# 03_-_OUT__5V7_OCXO_PROTECTION.net
KiCad netlist of a schematic drawn in Altium Designer
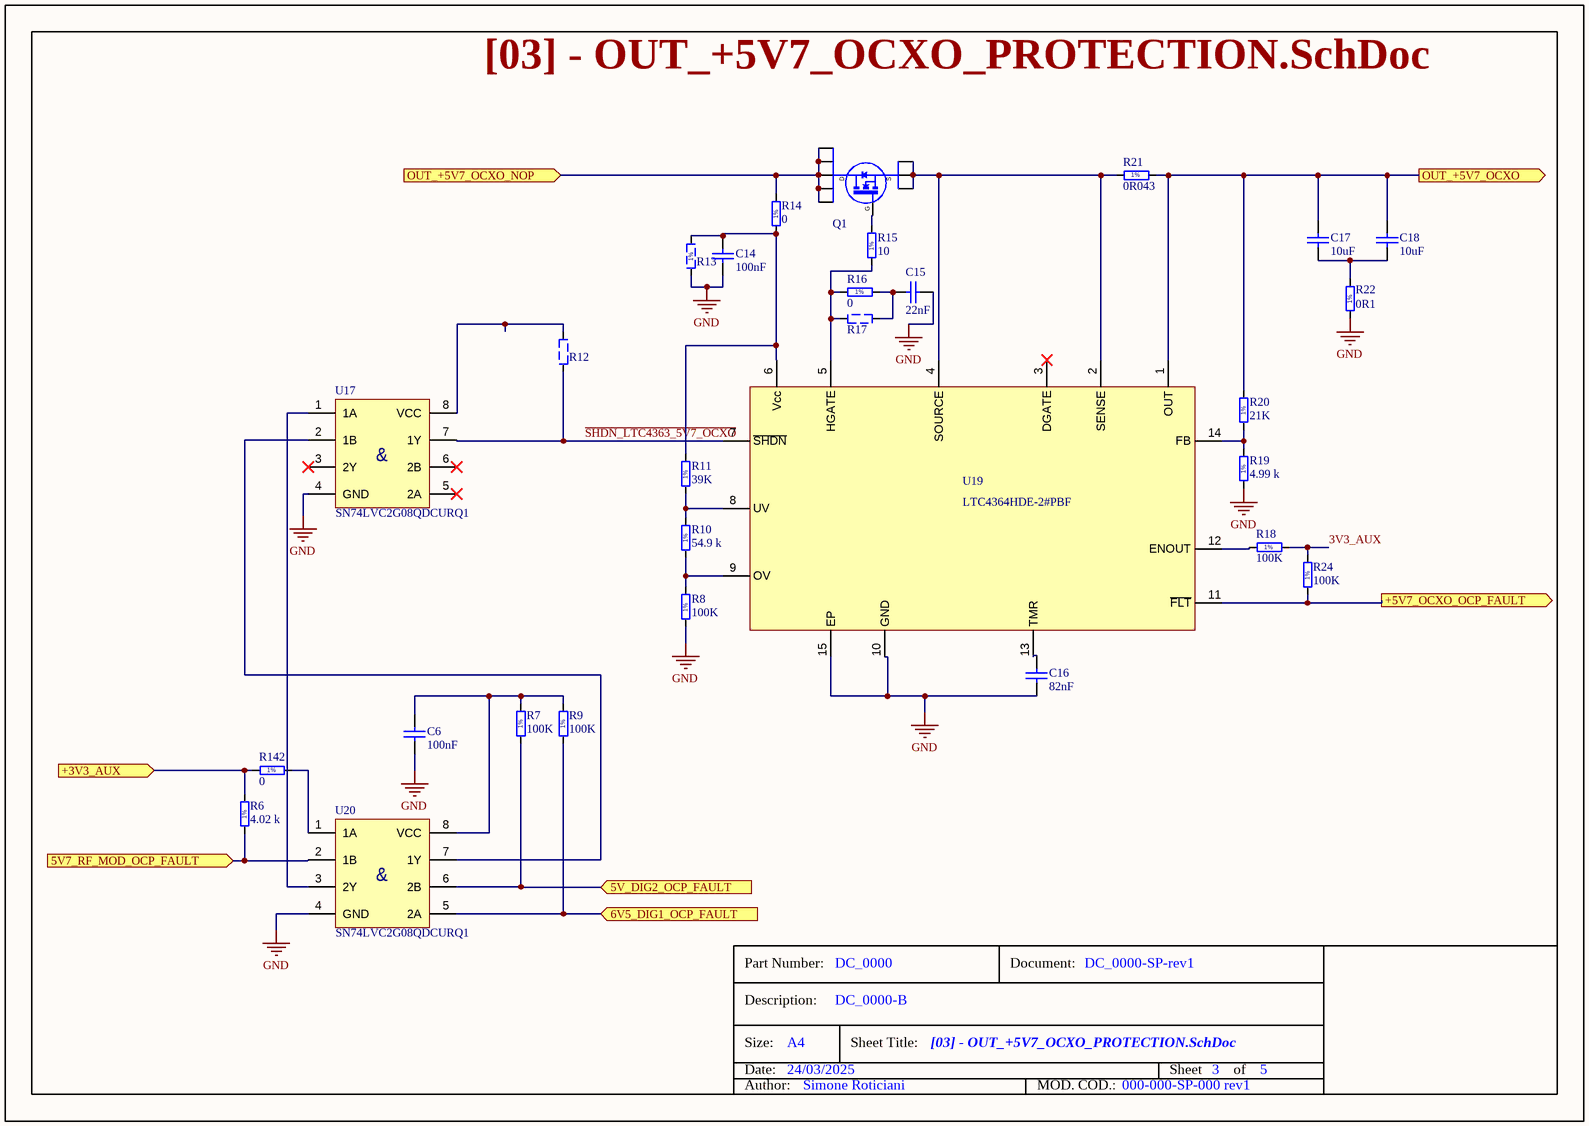
[diagram p0: [03] - OUT_+5V7_OCXO_PROTECTION.SchDoc]

(export (version "E")
  (design (tool "Eeschema 10.0.6"))
  (components
    (comp (ref "C6")
      (value "100nF")
      (footprint "CAPC100X50X55L25N")
      (description "CAP CER 100nF 50V ±10% X7R 0402")
      (fields (field (name "TOLERANCE") "±10%"))
      (libsource (lib "W_Preferiti") (part "C1005X7R1H104K050BB"))
    )
    (comp (ref "C14")
      (value "100nF")
      (footprint "CAPC100X50X55L25N")
      (description "CAP CER 100nF 50V ±10% X7R 0402")
      (fields
        (field (name "MANUFACTURER") "TDK")
        (field (name "MANUFACTURER PART NUMBER") "C1005X7R1H104K050BB")
      )
      (libsource (lib "W_Passive") (part "C1005X7R1H104K050BB"))
    )
    (comp (ref "C15")
      (value "22nF")
      (footprint "CAPC160X80X90L35N")
      (description "CAP CER 22nF 50V ±10% X7R 0603")
      (fields (field (name "TOLERANCE") "±10%"))
      (libsource (lib "W_Passive") (part "885012206091"))
    )
    (comp (ref "C16")
      (value "82nF")
      (footprint "CAPC160X80X90L35N")
      (description "CAP CER 82nF 50V ±10% X7R 0603")
      (fields (field (name "TOLERANCE") "±10%") (field (name "MANUFACTURER") "KYOCERA AVX"))
      (libsource (lib "W_Passive") (part "KAM15AR71H823KT"))
    )
    (comp (ref "C17")
      (value "10uF")
      (footprint "CAPC320X160X180L55N")
      (description "CAP CER 10UF 50V X7R 1206")
      (fields
        (field (name "MANUFACTURER") "TDK")
        (field (name "MANUFACTURER PART NUMBER") "C3216X7R1H106K160AC")
      )
      (libsource (lib "W_Passive") (part "C3216X7R1H106K160AC"))
    )
    (comp (ref "C18")
      (value "10uF")
      (footprint "CAPC320X160X180L55N")
      (description "CAP CER 10UF 50V X7R 1206")
      (fields
        (field (name "MANUFACTURER") "TDK")
        (field (name "MANUFACTURER PART NUMBER") "C3216X7R1H106K160AC")
      )
      (libsource (lib "W_Passive") (part "C3216X7R1H106K160AC"))
    )
    (comp (ref "Q1")
      (value "SI7414DN-T1-GE3")
      (footprint "Vishay PowerPAK 1212-8 package")
      (description "MOSFET N-CH 60V 5.6A PPAK1212-8")
      (fields (field (name "MANUFACTURER") "Vishay Siliconix"))
      (libsource (lib "W_IC") (part "SI7414DN-T1-GE3"))
    )
    (comp (ref "R6")
      (value "4.02 k")
      (footprint "RESC100X50X40L25N")
      (description "RES 4K02 OHM 1/16W 1% 0402")
      (fields (field (name "TOLERANCE") "±1%") (field (name "MANUFACTURER") "Vishay Dale"))
      (libsource (lib "W_Passive") (part "CRCW04024K02FKED"))
    )
    (comp (ref "R7")
      (value "100K")
      (footprint "RESC100X50X40L25N")
      (description "RES 100K OHM 1/16W 1% 0402")
      (fields
        (field (name "MANUFACTURER") "Vishay")
        (field (name "MANUFACTURER PART NUMBER") "CRCW0402100KFKEDC")
      )
      (libsource (lib "W_Preferiti") (part "CRCW0402100KFKEDC"))
    )
    (comp (ref "R8")
      (value "100K")
      (footprint "RESC100X50X40L25N")
      (description "RES 100K OHM 1/16W 1% 0402")
      (fields
        (field (name "MANUFACTURER") "Vishay")
        (field (name "MANUFACTURER PART NUMBER") "CRCW0402100KFKEDC")
      )
      (libsource (lib "W_Preferiti") (part "CRCW0402100KFKEDC"))
    )
    (comp (ref "R9")
      (value "100K")
      (footprint "RESC100X50X40L25N")
      (description "RES 100K OHM 1/16W 1% 0402")
      (fields
        (field (name "MANUFACTURER") "Vishay")
        (field (name "MANUFACTURER PART NUMBER") "CRCW0402100KFKEDC")
      )
      (libsource (lib "W_Preferiti") (part "CRCW0402100KFKEDC"))
    )
    (comp (ref "R10")
      (value "54.9 k")
      (footprint "RESC100X50X40L25N")
      (description "RES 54K9 OHM 1/16W 1% 0402")
      (fields (field (name "TOLERANCE") "±1%") (field (name "MANUFACTURER") "Vishay Dale"))
      (libsource (lib "W_Passive") (part "CRCW040254K9FKED"))
    )
    (comp (ref "R11")
      (value "39K")
      (footprint "RESC100X50X40L25N")
      (description "RES 39K OHM 1/16W 1% 0402")
      (fields (field (name "TOLERANCE") "±1%") (field (name "MANUFACTURER") "Vishay Dale"))
      (libsource (lib "W_Passive") (part "CRCW040239K0FKED"))
    )
    (comp (ref "R12")
      (value "NoBom")
      (footprint "RESC1608X50N")
      (description "Resistore Non in BOM")
      (libsource (lib "W_Passive") (part "1RES_NO_BOM"))
    )
    (comp (ref "R13")
      (value "NoBom")
      (footprint "RESC155X85X55L30N - NO BOM")
      (description "Resistore Non in BOM")
      (libsource (lib "W_Passive") (part "1RES_NO_BOM_0603"))
    )
    (comp (ref "R14")
      (value "0")
      (footprint "RESC155X85X55L30N")
      (description "RES 0 OHM 1/10W 1% 0603")
      (fields
        (field (name "MANUFACTURER") "Stackpole Electronics Inc")
        (field (name "MANUFACTURER PART NUMBER") "RMCF0603ZT0R00")
      )
      (libsource (lib "W_Preferiti") (part "RMCF0603ZT0R00"))
    )
    (comp (ref "R15")
      (value "10")
      (footprint "RESC100X50X40L25N")
      (description "RES 10 OHM 1/16W 1% 0402")
      (fields (field (name "TOLERANCE") "±1%") (field (name "MANUFACTURER") "Vishay Dale"))
      (libsource (lib "W_Passive") (part "CRCW040210R0FKED"))
    )
    (comp (ref "R16")
      (value "0")
      (footprint "RESC100X50X40L25N")
      (description "RES 0 OHM 1/16W 1% 0402")
      (fields
        (field (name "MANUFACTURER") "Vishay")
        (field (name "MANUFACTURER PART NUMBER") "CRCW04020000Z0EDC")
      )
      (libsource (lib "W_Preferiti") (part "CRCW04020000Z0EDC"))
    )
    (comp (ref "R17")
      (value "NoBom")
      (footprint "RESC1608X50N")
      (description "Resistore Non in BOM")
      (libsource (lib "W_Passive") (part "1RES_NO_BOM"))
    )
    (comp (ref "R18")
      (value "100K")
      (footprint "RESC100X50X40L25N")
      (description "RES 100K OHM 1/16W 1% 0402")
      (fields
        (field (name "MANUFACTURER") "Vishay")
        (field (name "MANUFACTURER PART NUMBER") "CRCW0402100KFKEDC")
      )
      (libsource (lib "W_Preferiti") (part "CRCW0402100KFKEDC"))
    )
    (comp (ref "R19")
      (value "4.99 k")
      (footprint "RESC100X50X40L25N")
      (description "RES 4K99 OHM 1/16W 1% 0402")
      (fields (field (name "TOLERANCE") "±1%") (field (name "MANUFACTURER") "Vishay Dale"))
      (libsource (lib "W_Passive") (part "CRCW04024K99FKED"))
    )
    (comp (ref "R20")
      (value "21K")
      (footprint "RESC100X50X40L25N")
      (description "RES 21K OHM 1/16W 1% 0402")
      (fields (field (name "TOLERANCE") "±1%") (field (name "MANUFACTURER") "Vishay Dale"))
      (libsource (lib "W_Passive") (part "CRCW040221K0FKED"))
    )
    (comp (ref "R21")
      (value "0R043")
      (footprint "RESC315X160X65L50N")
      (description "RES 0R043 OHM 1W 1% 1206")
      (fields
        (field (name "MANUFACTURER") "Littelfuse")
        (field (name "MANUFACTURER PART NUMBER") "WSTM1206QLR043FNR")
      )
      (libsource (lib "W_Passive") (part "WSTM1206QLR043FNR"))
    )
    (comp (ref "R22")
      (value "0R1")
      (footprint "RESC100X50X40L25N")
      (description "RES 0R1 OHM 1/10W 1% 0402")
      (fields
        (field (name "MANUFACTURER") "Samsung Electro-Mechanics America, Inc.")
        (field (name "MANUFACTURER PART NUMBER") "RUT1005FR100CS")
      )
      (libsource (lib "W_Passive") (part "RUT1005FR100CS"))
    )
    (comp (ref "R24")
      (value "100K")
      (footprint "RESC100X50X40L25N")
      (description "RES 100K OHM 1/16W 1% 0402")
      (fields
        (field (name "MANUFACTURER") "Vishay")
        (field (name "MANUFACTURER PART NUMBER") "CRCW0402100KFKEDC")
      )
      (libsource (lib "W_Preferiti") (part "CRCW0402100KFKEDC"))
    )
    (comp (ref "R142")
      (value "0")
      (footprint "RESC100X50X40L25N")
      (description "RES 0 OHM 1/16W 1% 0402")
      (fields
        (field (name "MANUFACTURER") "Vishay")
        (field (name "MANUFACTURER PART NUMBER") "CRCW04020000Z0EDC")
      )
      (libsource (lib "W_Preferiti") (part "CRCW04020000Z0EDC"))
    )
    (comp (ref "U17")
      (value "SN74LVC2G08QDCURQ1")
      (footprint "SOP50P310X90-8N")
      (description "Automotive 2-ch, 2-input, 1.65-V to 5.5-V AND gates 8-VSSOP -40 to 125")
      (fields (field (name "MANUFACTURER") "Texas Instruments"))
      (libsource (lib "W_IC") (part "SN74LVC2G08QDCURQ1"))
    )
    (comp (ref "U19")
      (value "LTC4364HDE-2#PBF")
      (footprint "DFN15P50_300X400X80L40X30T175X335")
      (description "Hot Swap Controller 1-CH 80V N-Channel Positive High Voltage Automotive 14-Pin DFN EP Tube")
      (fields (field (name "MANUFACTURER") "Analog Devices / Linear Technology"))
      (libsource (lib "W_IC") (part "LTC4364HDE-2#PBF"))
    )
    (comp (ref "U20")
      (value "SN74LVC2G08QDCURQ1")
      (footprint "SOP50P310X90-8N")
      (description "Automotive 2-ch, 2-input, 1.65-V to 5.5-V AND gates 8-VSSOP -40 to 125")
      (fields (field (name "MANUFACTURER") "Texas Instruments"))
      (libsource (lib "W_IC") (part "SN74LVC2G08QDCURQ1"))
    )
  )
  (nets
    (net (code "1") (name "/+3V3_AUX") (class "Default")
      (node (ref "R142") (pin "1") (pinfunction "1_1") (pintype "passive"))
      (node (ref "R6") (pin "2") (pinfunction "2_2") (pintype "passive"))
    )
    (net (code "2") (name "/+5V7_OCXO_OCP_FAULT") (class "Default")
      (node (ref "R24") (pin "1") (pinfunction "1_1") (pintype "passive"))
      (node (ref "U19") (pin "11") (pinfunction "~{FLT}_11") (pintype "passive"))
    )
    (net (code "3") (name "/3V3_AUX") (class "Default")
      (node (ref "R18") (pin "2") (pinfunction "2_2") (pintype "passive"))
      (node (ref "R24") (pin "2") (pinfunction "2_2") (pintype "passive"))
    )
    (net (code "4") (name "/5V7_RF_MOD_OCP_FAULT") (class "Default")
      (node (ref "R6") (pin "1") (pinfunction "1_1") (pintype "passive"))
      (node (ref "U20") (pin "2") (pinfunction "1B_2") (pintype "passive"))
    )
    (net (code "5") (name "/5V_DIG2_OCP_FAULT") (class "Default")
      (node (ref "R7") (pin "1") (pinfunction "1_1") (pintype "passive"))
      (node (ref "U20") (pin "6") (pinfunction "2B_6") (pintype "passive"))
    )
    (net (code "6") (name "/6V5_DIG1_OCP_FAULT") (class "Default")
      (node (ref "R9") (pin "1") (pinfunction "1_1") (pintype "passive"))
      (node (ref "U20") (pin "5") (pinfunction "2A_5") (pintype "passive"))
    )
    (net (code "7") (name "/OUT_+5V7_OCXO") (class "Default")
      (node (ref "C17") (pin "2") (pinfunction "2_2") (pintype "passive"))
      (node (ref "C18") (pin "2") (pinfunction "2_2") (pintype "passive"))
      (node (ref "R20") (pin "2") (pinfunction "2_2") (pintype "passive"))
      (node (ref "R21") (pin "2") (pinfunction "2_2") (pintype "passive"))
      (node (ref "U19") (pin "1") (pinfunction "OUT_1") (pintype "passive"))
    )
    (net (code "8") (name "/OUT_+5V7_OCXO_NOP") (class "Default")
      (node (ref "Q1") (pin "5") (pinfunction "D_5") (pintype "passive"))
      (node (ref "Q1") (pin "6") (pinfunction "D_6") (pintype "passive"))
      (node (ref "Q1") (pin "7") (pinfunction "D_7") (pintype "passive"))
      (node (ref "Q1") (pin "8") (pinfunction "D_8") (pintype "passive"))
      (node (ref "Q1") (pin "9") (pinfunction "D_9") (pintype "passive"))
      (node (ref "R14") (pin "2") (pinfunction "2_2") (pintype "passive"))
    )
    (net (code "9") (name "/~{SHDN_LTC4363_5V7_OCXO}") (class "Default")
      (node (ref "R12") (pin "1") (pinfunction "1_1") (pintype "passive"))
      (node (ref "U17") (pin "7") (pinfunction "1Y_7") (pintype "passive"))
      (node (ref "U19") (pin "7") (pinfunction "~{SHDN}_7") (pintype "passive"))
    )
    (net (code "10") (name "GND") (class "Default")
      (node (ref "C14") (pin "1") (pinfunction "1_1") (pintype "passive"))
      (node (ref "C15") (pin "2") (pinfunction "2_2") (pintype "passive"))
      (node (ref "C16") (pin "1") (pinfunction "1_1") (pintype "passive"))
      (node (ref "C6") (pin "1") (pinfunction "1_1") (pintype "passive"))
      (node (ref "R13") (pin "1") (pinfunction "1_1") (pintype "passive"))
      (node (ref "R19") (pin "1") (pinfunction "1_1") (pintype "passive"))
      (node (ref "R22") (pin "1") (pinfunction "1_1") (pintype "passive"))
      (node (ref "R8") (pin "1") (pinfunction "1_1") (pintype "passive"))
      (node (ref "U17") (pin "4") (pinfunction "GND_4") (pintype "passive"))
      (node (ref "U19") (pin "10") (pinfunction "GND_10") (pintype "passive"))
      (node (ref "U19") (pin "15") (pinfunction "EP_15") (pintype "passive"))
      (node (ref "U20") (pin "4") (pinfunction "GND_4") (pintype "passive"))
    )
    (net (code "11") (name "Net-(C15-Pad1)") (class "Default")
      (node (ref "C15") (pin "1") (pinfunction "1_1") (pintype "passive"))
      (node (ref "R16") (pin "2") (pinfunction "2_2") (pintype "passive"))
      (node (ref "R17") (pin "2") (pinfunction "2_2") (pintype "passive"))
    )
    (net (code "12") (name "Net-(C17-Pad1)") (class "Default")
      (node (ref "C17") (pin "1") (pinfunction "1_1") (pintype "passive"))
      (node (ref "C18") (pin "1") (pinfunction "1_1") (pintype "passive"))
      (node (ref "R22") (pin "2") (pinfunction "2_2") (pintype "passive"))
    )
    (net (code "13") (name "Net-(Q1-G)") (class "Default")
      (node (ref "Q1") (pin "4") (pinfunction "G_4") (pintype "passive"))
      (node (ref "R15") (pin "2") (pinfunction "2_2") (pintype "passive"))
    )
    (net (code "14") (name "Net-(U17-1A)") (class "Default")
      (node (ref "U17") (pin "1") (pinfunction "1A_1") (pintype "passive"))
      (node (ref "U20") (pin "3") (pinfunction "2Y_3") (pintype "passive"))
    )
    (net (code "15") (name "Net-(U17-1B)") (class "Default")
      (node (ref "U17") (pin "2") (pinfunction "1B_2") (pintype "passive"))
      (node (ref "U20") (pin "7") (pinfunction "1Y_7") (pintype "passive"))
    )
    (net (code "16") (name "Net-(U17-VCC)") (class "Default")
      (node (ref "R12") (pin "2") (pinfunction "2_2") (pintype "passive"))
      (node (ref "U17") (pin "8") (pinfunction "VCC_8") (pintype "passive"))
    )
    (net (code "17") (name "Net-(U19-ENOUT)") (class "Default")
      (node (ref "R18") (pin "1") (pinfunction "1_1") (pintype "passive"))
      (node (ref "U19") (pin "12") (pinfunction "ENOUT_12") (pintype "passive"))
    )
    (net (code "18") (name "Net-(U19-FB)") (class "Default")
      (node (ref "R19") (pin "2") (pinfunction "2_2") (pintype "passive"))
      (node (ref "R20") (pin "1") (pinfunction "1_1") (pintype "passive"))
      (node (ref "U19") (pin "14") (pinfunction "FB_14") (pintype "passive"))
    )
    (net (code "19") (name "Net-(U19-HGATE)") (class "Default")
      (node (ref "R15") (pin "1") (pinfunction "1_1") (pintype "passive"))
      (node (ref "R16") (pin "1") (pinfunction "1_1") (pintype "passive"))
      (node (ref "R17") (pin "1") (pinfunction "1_1") (pintype "passive"))
      (node (ref "U19") (pin "5") (pinfunction "HGATE_5") (pintype "passive"))
    )
    (net (code "20") (name "Net-(U19-OV)") (class "Default")
      (node (ref "R10") (pin "1") (pinfunction "1_1") (pintype "passive"))
      (node (ref "R8") (pin "2") (pinfunction "2_2") (pintype "passive"))
      (node (ref "U19") (pin "9") (pinfunction "OV_9") (pintype "passive"))
    )
    (net (code "21") (name "Net-(U19-SENSE)") (class "Default")
      (node (ref "Q1") (pin "1") (pinfunction "S_1") (pintype "passive"))
      (node (ref "Q1") (pin "2") (pinfunction "S_2") (pintype "passive"))
      (node (ref "Q1") (pin "3") (pinfunction "S_3") (pintype "passive"))
      (node (ref "R21") (pin "1") (pinfunction "1_1") (pintype "passive"))
      (node (ref "U19") (pin "2") (pinfunction "SENSE_2") (pintype "passive"))
      (node (ref "U19") (pin "4") (pinfunction "SOURCE_4") (pintype "passive"))
    )
    (net (code "22") (name "Net-(U19-TMR)") (class "Default")
      (node (ref "C16") (pin "2") (pinfunction "2_2") (pintype "passive"))
      (node (ref "U19") (pin "13") (pinfunction "TMR_13") (pintype "passive"))
    )
    (net (code "23") (name "Net-(U19-UV)") (class "Default")
      (node (ref "R10") (pin "2") (pinfunction "2_2") (pintype "passive"))
      (node (ref "R11") (pin "1") (pinfunction "1_1") (pintype "passive"))
      (node (ref "U19") (pin "8") (pinfunction "UV_8") (pintype "passive"))
    )
    (net (code "24") (name "Net-(U19-Vcc)") (class "Default")
      (node (ref "C14") (pin "2") (pinfunction "2_2") (pintype "passive"))
      (node (ref "R11") (pin "2") (pinfunction "2_2") (pintype "passive"))
      (node (ref "R13") (pin "2") (pinfunction "2_2") (pintype "passive"))
      (node (ref "R14") (pin "1") (pinfunction "1_1") (pintype "passive"))
      (node (ref "U19") (pin "6") (pinfunction "Vcc_6") (pintype "passive"))
    )
    (net (code "25") (name "Net-(U20-1A)") (class "Default")
      (node (ref "R142") (pin "2") (pinfunction "2_2") (pintype "passive"))
      (node (ref "U20") (pin "1") (pinfunction "1A_1") (pintype "passive"))
    )
    (net (code "26") (name "Net-(U20-VCC)") (class "Default")
      (node (ref "C6") (pin "2") (pinfunction "2_2") (pintype "passive"))
      (node (ref "R7") (pin "2") (pinfunction "2_2") (pintype "passive"))
      (node (ref "R9") (pin "2") (pinfunction "2_2") (pintype "passive"))
      (node (ref "U20") (pin "8") (pinfunction "VCC_8") (pintype "passive"))
    )
    (net (code "27") (name "unconnected-(U17-2A-Pad5)") (class "Default")
      (node (ref "U17") (pin "5") (pinfunction "2A_5") (pintype "passive+no_connect"))
    )
    (net (code "28") (name "unconnected-(U17-2B-Pad6)") (class "Default")
      (node (ref "U17") (pin "6") (pinfunction "2B_6") (pintype "passive+no_connect"))
    )
    (net (code "29") (name "unconnected-(U17-2Y-Pad3)") (class "Default")
      (node (ref "U17") (pin "3") (pinfunction "2Y_3") (pintype "passive+no_connect"))
    )
    (net (code "30") (name "unconnected-(U19-DGATE-Pad3)") (class "Default")
      (node (ref "U19") (pin "3") (pinfunction "DGATE_3") (pintype "passive+no_connect"))
    )
  )
)
